# STMOD.net
KiCad netlist of a schematic drawn in Altium Designer
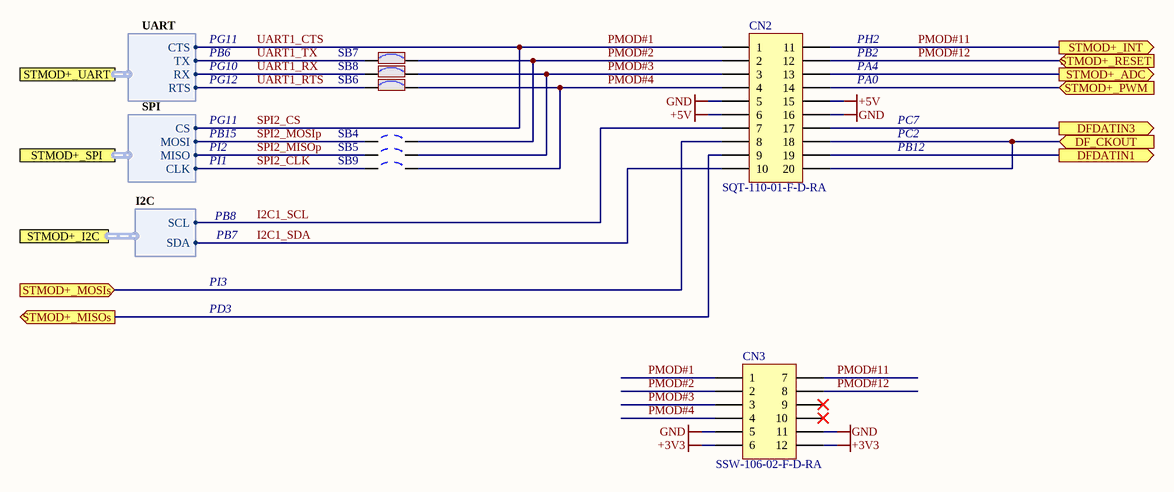
[diagram p0: STMOD+.SchDoc]

(export (version "E")
  (design (tool "Eeschema 10.0.6"))
  (components
    (comp (ref "CN2")
      (value "SQT-110-01-F-D-RA")
      (footprint "SQT-110-01-F-D-RA")
      (description "Header, 10-Pin, Dual row")
      (libsource (lib "Miscellaneous Connectors") (part "Header 10X2A"))
    )
    (comp (ref "CN3")
      (value "SSW-106-02-F-D-RA")
      (footprint "SSW-106-02-F-D-RA")
      (description "Header, 6-Pin, Dual row")
      (libsource (lib "Miscellaneous Connectors") (part "Header 6X2A"))
    )
    (comp (ref "SB4")
      (value "Solder Bridge OFF")
      (footprint "SB_0603")
      (libsource (lib "MCD_TOOLS") (part "SB_OFF"))
    )
    (comp (ref "SB5")
      (value "Solder Bridge OFF")
      (footprint "SB_0603")
      (libsource (lib "MCD_TOOLS") (part "SB_OFF"))
    )
    (comp (ref "SB6")
      (value "Solder Bridge ON")
      (footprint "SB_0603")
      (libsource (lib "MCD_TOOLS") (part "SB_ON"))
    )
    (comp (ref "SB7")
      (value "Solder Bridge ON")
      (footprint "SB_0603")
      (libsource (lib "MCD_TOOLS") (part "SB_ON"))
    )
    (comp (ref "SB8")
      (value "Solder Bridge ON")
      (footprint "SB_0603")
      (libsource (lib "MCD_TOOLS") (part "SB_ON"))
    )
    (comp (ref "SB9")
      (value "Solder Bridge OFF")
      (footprint "SB_0603")
      (libsource (lib "MCD_TOOLS") (part "SB_OFF"))
    )
  )
  (nets
    (net (code "4") (name "+3V3") (class "Default")
      (node (ref "CN3") (pin "12") (pinfunction "12_12") (pintype "passive"))
      (node (ref "CN3") (pin "6") (pinfunction "6_6") (pintype "passive"))
    )
    (net (code "5") (name "+5V") (class "Default")
      (node (ref "CN2") (pin "15") (pinfunction "15_15") (pintype "passive"))
      (node (ref "CN2") (pin "6") (pinfunction "6_6") (pintype "passive"))
    )
    (net (code "6") (name "/DFDATIN1") (class "Default")
      (node (ref "CN2") (pin "19") (pinfunction "19_19") (pintype "passive"))
    )
    (net (code "7") (name "/DFDATIN3") (class "Default")
      (node (ref "CN2") (pin "17") (pinfunction "17_17") (pintype "passive"))
    )
    (net (code "8") (name "/DF_CKOUT") (class "Default")
      (node (ref "CN2") (pin "18") (pinfunction "18_18") (pintype "passive"))
      (node (ref "CN2") (pin "20") (pinfunction "20_20") (pintype "passive"))
    )
    (net (code "9") (name "/I2C1_SCL") (class "Default")
      (node (ref "CN2") (pin "7") (pinfunction "7_7") (pintype "passive"))
    )
    (net (code "10") (name "/I2C1_SDA") (class "Default")
      (node (ref "CN2") (pin "10") (pinfunction "10_10") (pintype "passive"))
    )
    (net (code "11") (name "/PMOD#1") (class "Default")
      (node (ref "CN2") (pin "1") (pinfunction "1_1") (pintype "passive"))
      (node (ref "CN3") (pin "1") (pinfunction "1_1") (pintype "passive"))
    )
    (net (code "12") (name "/PMOD#2") (class "Default")
      (node (ref "CN2") (pin "2") (pinfunction "2_2") (pintype "passive"))
      (node (ref "CN3") (pin "2") (pinfunction "2_2") (pintype "passive"))
      (node (ref "SB4") (pin "2") (pinfunction "2_2") (pintype "passive"))
      (node (ref "SB7") (pin "2") (pinfunction "2_2") (pintype "passive"))
    )
    (net (code "13") (name "/PMOD#3") (class "Default")
      (node (ref "CN2") (pin "3") (pinfunction "3_3") (pintype "passive"))
      (node (ref "CN3") (pin "3") (pinfunction "3_3") (pintype "passive"))
      (node (ref "SB5") (pin "2") (pinfunction "2_2") (pintype "passive"))
      (node (ref "SB8") (pin "2") (pinfunction "2_2") (pintype "passive"))
    )
    (net (code "14") (name "/PMOD#4") (class "Default")
      (node (ref "CN2") (pin "4") (pinfunction "4_4") (pintype "passive"))
      (node (ref "CN3") (pin "4") (pinfunction "4_4") (pintype "passive"))
      (node (ref "SB6") (pin "2") (pinfunction "2_2") (pintype "passive"))
      (node (ref "SB9") (pin "2") (pinfunction "2_2") (pintype "passive"))
    )
    (net (code "15") (name "/PMOD#11") (class "Default")
      (node (ref "CN2") (pin "11") (pinfunction "11_11") (pintype "passive"))
      (node (ref "CN3") (pin "7") (pinfunction "7_7") (pintype "passive"))
    )
    (net (code "16") (name "/PMOD#12") (class "Default")
      (node (ref "CN2") (pin "12") (pinfunction "12_12") (pintype "passive"))
      (node (ref "CN3") (pin "8") (pinfunction "8_8") (pintype "passive"))
    )
    (net (code "17") (name "/SPI2_CLK") (class "Default")
      (node (ref "SB9") (pin "1") (pinfunction "1_1") (pintype "passive"))
    )
    (net (code "18") (name "/SPI2_MISOp") (class "Default")
      (node (ref "SB5") (pin "1") (pinfunction "1_1") (pintype "passive"))
    )
    (net (code "19") (name "/SPI2_MOSIp") (class "Default")
      (node (ref "SB4") (pin "1") (pinfunction "1_1") (pintype "passive"))
    )
    (net (code "20") (name "/STMOD+_ADC") (class "Default")
      (node (ref "CN2") (pin "13") (pinfunction "13_13") (pintype "passive"))
    )
    (net (code "21") (name "/STMOD+_MISOs") (class "Default")
      (node (ref "CN2") (pin "9") (pinfunction "9_9") (pintype "passive"))
    )
    (net (code "22") (name "/STMOD+_MOSIs") (class "Default")
      (node (ref "CN2") (pin "8") (pinfunction "8_8") (pintype "passive"))
    )
    (net (code "23") (name "/STMOD+_PWM") (class "Default")
      (node (ref "CN2") (pin "14") (pinfunction "14_14") (pintype "passive"))
    )
    (net (code "24") (name "/UART1_RTS") (class "Default")
      (node (ref "SB6") (pin "1") (pinfunction "1_1") (pintype "passive"))
    )
    (net (code "25") (name "/UART1_RX") (class "Default")
      (node (ref "SB8") (pin "1") (pinfunction "1_1") (pintype "passive"))
    )
    (net (code "26") (name "/UART1_TX") (class "Default")
      (node (ref "SB7") (pin "1") (pinfunction "1_1") (pintype "passive"))
    )
    (net (code "30") (name "GND") (class "Default")
      (node (ref "CN2") (pin "16") (pinfunction "16_16") (pintype "passive"))
      (node (ref "CN2") (pin "5") (pinfunction "5_5") (pintype "passive"))
      (node (ref "CN3") (pin "11") (pinfunction "11_11") (pintype "passive"))
      (node (ref "CN3") (pin "5") (pinfunction "5_5") (pintype "passive"))
    )
    (net (code "31") (name "unconnected-(CN3-Pad9)") (class "Default")
      (node (ref "CN3") (pin "9") (pinfunction "9_9") (pintype "passive+no_connect"))
    )
    (net (code "32") (name "unconnected-(CN3-Pad10)") (class "Default")
      (node (ref "CN3") (pin "10") (pinfunction "10_10") (pintype "passive+no_connect"))
    )
  )
)
